# 01__Controllers_Sheet.net
KiCad netlist of a schematic drawn in Altium Designer
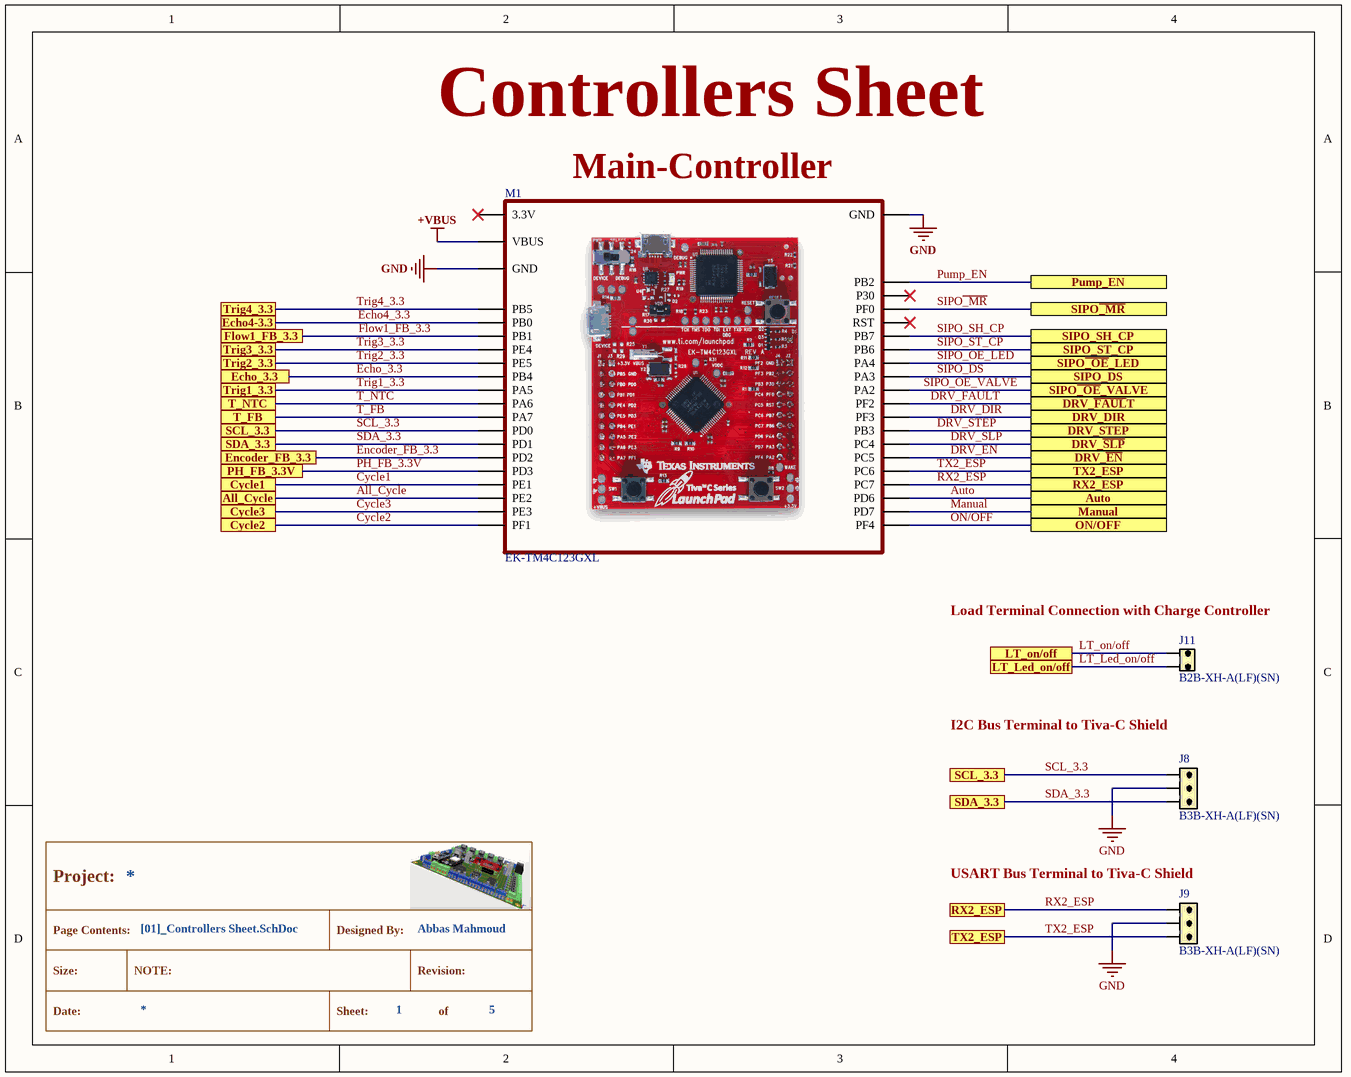
[diagram p0: [01]_Controllers Sheet.SchDoc]

(export (version "E")
  (design (tool "Eeschema 10.0.6"))
  (components
    (comp (ref "*")
      (value "Title Block")
      (description "Moatley Title Block")
      (libsource (lib "Altium_Abbas") (part "Title Block"))
    )
    (comp (ref "J8")
      (value "B3B-XH-A(LF)(SN)")
      (footprint "XH - 3P - Vertical - Package - THT - P = 2.54")
      (fields (field (name "MANUFACTURER") "JST Sales America"))
      (libsource (lib "Altium_Abbas_V3") (part "XH - Male Header - 3P - THT - Vertical"))
    )
    (comp (ref "J9")
      (value "B3B-XH-A(LF)(SN)")
      (footprint "XH - 3P - Vertical - Package - THT - P = 2.54")
      (fields (field (name "MANUFACTURER") "JST Sales America"))
      (libsource (lib "Altium_Abbas_V3") (part "XH - Male Header - 3P - THT - Vertical"))
    )
    (comp (ref "J11")
      (value "B2B-XH-A(LF)(SN)")
      (footprint "XH - 2P - Vertical - Package - THT - P = 2.54")
      (fields (field (name "MANUFACTURER") "JST Sales America"))
      (libsource (lib "Altium_Abbas_V3") (part "XH - Male Header - 2P - THT - Vertical"))
    )
    (comp (ref "M1")
      (value "EK-TM4C123GXL")
      (footprint "Tiva-C")
      (libsource (lib "Boards_Abbas") (part "Tiva-C"))
    )
  )
  (nets
    (net (code "1") (name "+VBUS") (class "Default")
      (node (ref "M1") (pin "VBUS") (pinfunction "VBUS_VBUS") (pintype "passive"))
    )
    (net (code "2") (name "/All_Cycle") (class "Default")
      (node (ref "M1") (pin "PE2") (pinfunction "PE2_PE2") (pintype "passive"))
    )
    (net (code "3") (name "/Auto") (class "Default")
      (node (ref "M1") (pin "PD6") (pinfunction "PD6_PD6") (pintype "passive"))
    )
    (net (code "4") (name "/Cycle1") (class "Default")
      (node (ref "M1") (pin "PE1") (pinfunction "PE1_PE1") (pintype "passive"))
    )
    (net (code "5") (name "/Cycle2") (class "Default")
      (node (ref "M1") (pin "PF1") (pinfunction "PF1_PF1") (pintype "passive"))
    )
    (net (code "6") (name "/Cycle3") (class "Default")
      (node (ref "M1") (pin "PE3") (pinfunction "PE3_PE3") (pintype "passive"))
    )
    (net (code "7") (name "/DRV_DIR") (class "Default")
      (node (ref "M1") (pin "PF3") (pinfunction "PF3_PF3") (pintype "passive"))
    )
    (net (code "8") (name "/DRV_STEP") (class "Default")
      (node (ref "M1") (pin "PB3") (pinfunction "PB3_PB3") (pintype "passive"))
    )
    (net (code "9") (name "/DRV_~{EN}") (class "Default")
      (node (ref "M1") (pin "PC5") (pinfunction "PC5_PC5") (pintype "passive"))
    )
    (net (code "10") (name "/DRV_~{FAULT}") (class "Default")
      (node (ref "M1") (pin "PF2") (pinfunction "PF2_PF2") (pintype "passive"))
    )
    (net (code "11") (name "/DRV_~{SLP}") (class "Default")
      (node (ref "M1") (pin "PC4") (pinfunction "PC4_PC4") (pintype "passive"))
    )
    (net (code "12") (name "/Echo4_3.3") (class "Default")
      (node (ref "M1") (pin "PB0") (pinfunction "PB0_PB0") (pintype "passive"))
    )
    (net (code "13") (name "/Echo_3.3") (class "Default")
      (node (ref "M1") (pin "PB4") (pinfunction "PB4_PB4") (pintype "passive"))
    )
    (net (code "14") (name "/Encoder_FB_3.3") (class "Default")
      (node (ref "M1") (pin "PD2") (pinfunction "PD2_PD2") (pintype "passive"))
    )
    (net (code "15") (name "/Flow1_FB_3.3") (class "Default")
      (node (ref "M1") (pin "PB1") (pinfunction "PB1_PB1") (pintype "passive"))
    )
    (net (code "16") (name "/LT_Led_on{slash}off") (class "Default")
      (node (ref "J11") (pin "2") (pinfunction "2_2") (pintype "passive"))
    )
    (net (code "17") (name "/LT_on{slash}off") (class "Default")
      (node (ref "J11") (pin "1") (pinfunction "1_1") (pintype "passive"))
    )
    (net (code "18") (name "/Manual") (class "Default")
      (node (ref "M1") (pin "PD7") (pinfunction "PD7_PD7") (pintype "passive"))
    )
    (net (code "19") (name "/ON{slash}OFF") (class "Default")
      (node (ref "M1") (pin "PF4") (pinfunction "PF4_PF4") (pintype "passive"))
    )
    (net (code "20") (name "/PH_FB_3.3V") (class "Default")
      (node (ref "M1") (pin "PD3") (pinfunction "PD3_PD3") (pintype "passive"))
    )
    (net (code "21") (name "/Pump_EN") (class "Default")
      (node (ref "M1") (pin "PB2") (pinfunction "PB2_PB2") (pintype "passive"))
    )
    (net (code "22") (name "/RX2_ESP") (class "Default")
      (node (ref "J9") (pin "1") (pinfunction "1_1") (pintype "passive"))
      (node (ref "M1") (pin "PC7") (pinfunction "PC7_PC7") (pintype "passive"))
    )
    (net (code "23") (name "/SCL_3.3") (class "Default")
      (node (ref "J8") (pin "1") (pinfunction "1_1") (pintype "passive"))
      (node (ref "M1") (pin "PD0") (pinfunction "PD0_PD0") (pintype "passive"))
    )
    (net (code "24") (name "/SDA_3.3") (class "Default")
      (node (ref "J8") (pin "3") (pinfunction "3_3") (pintype "passive"))
      (node (ref "M1") (pin "PD1") (pinfunction "PD1_PD1") (pintype "passive"))
    )
    (net (code "25") (name "/SIPO_DS") (class "Default")
      (node (ref "M1") (pin "PA3") (pinfunction "PA3_PA3") (pintype "passive"))
    )
    (net (code "26") (name "/SIPO_SH_CP") (class "Default")
      (node (ref "M1") (pin "PB7") (pinfunction "PB7_PB7") (pintype "passive"))
    )
    (net (code "27") (name "/SIPO_ST_CP") (class "Default")
      (node (ref "M1") (pin "PB6") (pinfunction "PB6_PB6") (pintype "passive"))
    )
    (net (code "28") (name "/SIPO~{_MR}") (class "Default")
      (node (ref "M1") (pin "PF0") (pinfunction "PF0_PF0") (pintype "passive"))
    )
    (net (code "29") (name "/SIPO~{_OE}_LED") (class "Default")
      (node (ref "M1") (pin "PA4") (pinfunction "PA4_PA4") (pintype "passive"))
    )
    (net (code "30") (name "/SIPO~{_OE}_VALVE") (class "Default")
      (node (ref "M1") (pin "PA2") (pinfunction "PA2_PA2") (pintype "passive"))
    )
    (net (code "31") (name "/TX2_ESP") (class "Default")
      (node (ref "J9") (pin "3") (pinfunction "3_3") (pintype "passive"))
      (node (ref "M1") (pin "PC6") (pinfunction "PC6_PC6") (pintype "passive"))
    )
    (net (code "32") (name "/T_FB") (class "Default")
      (node (ref "M1") (pin "PA7") (pinfunction "PA7_PA7") (pintype "passive"))
    )
    (net (code "33") (name "/T_NTC") (class "Default")
      (node (ref "M1") (pin "PA6") (pinfunction "PA6_PA6") (pintype "passive"))
    )
    (net (code "34") (name "/Trig1_3.3") (class "Default")
      (node (ref "M1") (pin "PA5") (pinfunction "PA5_PA5") (pintype "passive"))
    )
    (net (code "35") (name "/Trig2_3.3") (class "Default")
      (node (ref "M1") (pin "PE5") (pinfunction "PE5_PE5") (pintype "passive"))
    )
    (net (code "36") (name "/Trig3_3.3") (class "Default")
      (node (ref "M1") (pin "PE4") (pinfunction "PE4_PE4") (pintype "passive"))
    )
    (net (code "37") (name "/Trig4_3.3") (class "Default")
      (node (ref "M1") (pin "PB5") (pinfunction "PB5_PB5") (pintype "passive"))
    )
    (net (code "38") (name "GND") (class "Default")
      (node (ref "J8") (pin "2") (pinfunction "2_2") (pintype "passive"))
      (node (ref "J9") (pin "2") (pinfunction "2_2") (pintype "passive"))
      (node (ref "M1") (pin "GND") (pinfunction "GND_GND") (pintype "passive"))
    )
    (net (code "39") (name "unconnected-(M1-Pad3.3V)") (class "Default")
      (node (ref "M1") (pin "3.3V") (pinfunction "3.3V_3.3V") (pintype "passive+no_connect"))
    )
    (net (code "40") (name "unconnected-(M1-PadP30)") (class "Default")
      (node (ref "M1") (pin "P30") (pinfunction "P30_P30") (pintype "passive+no_connect"))
    )
    (net (code "41") (name "unconnected-(M1-PadRST)") (class "Default")
      (node (ref "M1") (pin "RST") (pinfunction "RST_RST") (pintype "passive+no_connect"))
    )
  )
)
